# wave.net
KiCad netlist of a schematic drawn in Altium Designer
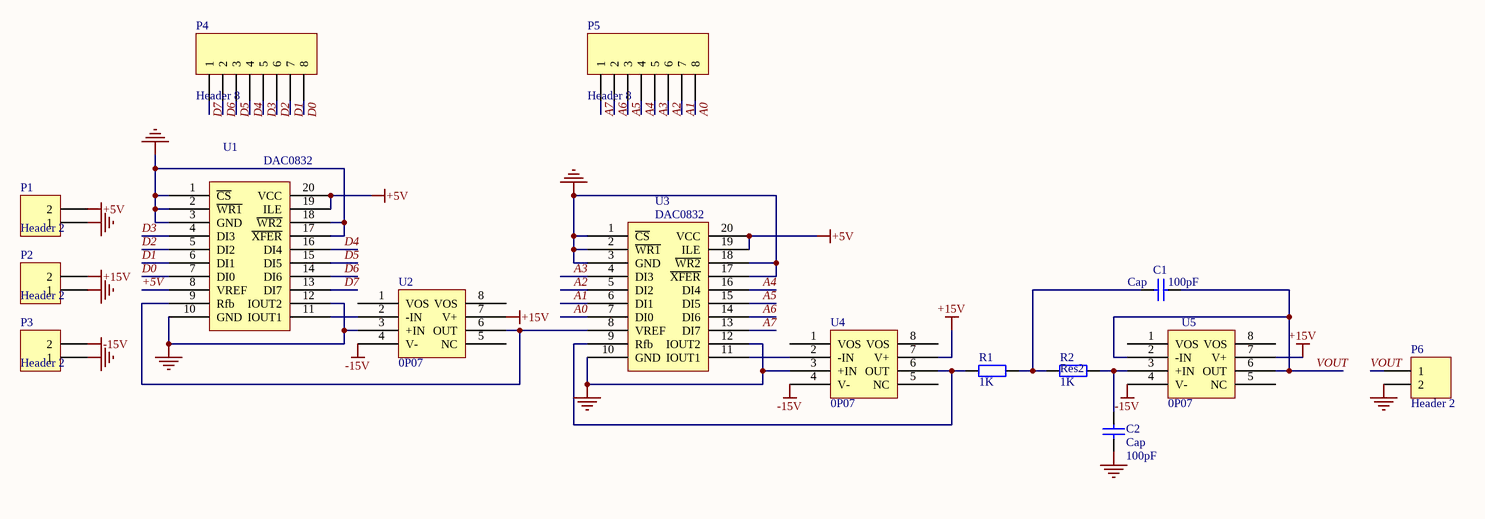
[diagram p0: wave.SchDoc]

(export (version "E")
  (design (tool "Eeschema 10.0.6"))
  (components
    (comp (ref "C1")
      (value "Cap")
      (footprint "RAD-0.3")
      (description "Capacitor")
      (fields (field (name "ALTIUM_VALUE") "100pF") (field (name "PUBLISHER") "Altium Limited"))
      (libsource (lib "Miscellaneous Devices") (part "Cap"))
    )
    (comp (ref "C2")
      (value "Cap")
      (footprint "RAD-0.3")
      (description "Capacitor")
      (fields (field (name "ALTIUM_VALUE") "100pF") (field (name "PUBLISHER") "Altium Limited"))
      (libsource (lib "Miscellaneous Devices") (part "Cap"))
    )
    (comp (ref "P1")
      (value "Header 2")
      (footprint "HDR1X2")
      (description "Header, 2-Pin")
      (fields (field (name "PUBLISHER") "Altium Limited"))
      (libsource (lib "Miscellaneous Connectors") (part "Header 2"))
    )
    (comp (ref "P2")
      (value "Header 2")
      (footprint "HDR1X2")
      (description "Header, 2-Pin")
      (fields (field (name "PUBLISHER") "Altium Limited"))
      (libsource (lib "Miscellaneous Connectors") (part "Header 2"))
    )
    (comp (ref "P3")
      (value "Header 2")
      (footprint "HDR1X2")
      (description "Header, 2-Pin")
      (fields (field (name "PUBLISHER") "Altium Limited"))
      (libsource (lib "Miscellaneous Connectors") (part "Header 2"))
    )
    (comp (ref "P4")
      (value "Header 8")
      (footprint "HDR1X8")
      (description "Header, 8-Pin")
      (fields (field (name "PUBLISHER") "Altium Limited"))
      (libsource (lib "Miscellaneous Connectors") (part "Header 8"))
    )
    (comp (ref "P5")
      (value "Header 8")
      (footprint "HDR1X8")
      (description "Header, 8-Pin")
      (fields (field (name "PUBLISHER") "Altium Limited"))
      (libsource (lib "Miscellaneous Connectors") (part "Header 8"))
    )
    (comp (ref "P6")
      (value "Header 2")
      (footprint "HDR1X2")
      (description "Header, 2-Pin")
      (fields (field (name "PUBLISHER") "Altium Limited"))
      (libsource (lib "") (part "Header 2_1"))
    )
    (comp (ref "R1")
      (value "1K")
      (footprint "AXIAL-0.4")
      (description "Resistor")
      (fields (field (name "Comment") "Res2") (field (name "PUBLISHER") "Altium Limited"))
      (libsource (lib "Miscellaneous Devices") (part "Res2"))
    )
    (comp (ref "R2")
      (value "Res2")
      (footprint "AXIAL-0.4")
      (description "Resistor")
      (fields (field (name "ALTIUM_VALUE") "1K") (field (name "PUBLISHER") "Altium Limited"))
      (libsource (lib "Miscellaneous Devices") (part "Res2"))
    )
    (comp (ref "U1")
      (value "DAC0832")
      (footprint "DIP-20")
      (libsource (lib "My sch Library") (part "DAC0832"))
    )
    (comp (ref "U2") (value "0P07") (footprint "DIP-8") (libsource (lib "My sch Library") (part "OP07")))
    (comp (ref "U3")
      (value "DAC0832")
      (footprint "DIP-20")
      (libsource (lib "My sch Library") (part "DAC0832"))
    )
    (comp (ref "U4") (value "0P07") (footprint "DIP-8") (libsource (lib "My sch Library") (part "OP07")))
    (comp (ref "U5") (value "0P07") (footprint "DIP-8") (libsource (lib "My sch Library") (part "OP07")))
  )
  (nets
    (net (code "1") (name "+5V") (class "Default")
      (node (ref "P1") (pin "2") (pinfunction "2_2") (pintype "passive"))
      (node (ref "U1") (pin "19") (pinfunction "ILE_19") (pintype "passive"))
      (node (ref "U1") (pin "20") (pinfunction "VCC_20") (pintype "passive"))
      (node (ref "U1") (pin "8") (pinfunction "VREF_8") (pintype "passive"))
      (node (ref "U3") (pin "19") (pinfunction "ILE_19") (pintype "passive"))
      (node (ref "U3") (pin "20") (pinfunction "VCC_20") (pintype "passive"))
    )
    (net (code "2") (name "+15V") (class "Default")
      (node (ref "P2") (pin "2") (pinfunction "2_2") (pintype "passive"))
      (node (ref "U2") (pin "7") (pinfunction "V+_7") (pintype "passive"))
      (node (ref "U4") (pin "7") (pinfunction "V+_7") (pintype "passive"))
      (node (ref "U5") (pin "7") (pinfunction "V+_7") (pintype "passive"))
    )
    (net (code "3") (name "-15V") (class "Default")
      (node (ref "P3") (pin "2") (pinfunction "2_2") (pintype "passive"))
      (node (ref "U2") (pin "4") (pinfunction "V-_4") (pintype "passive"))
      (node (ref "U4") (pin "4") (pinfunction "V-_4") (pintype "passive"))
      (node (ref "U5") (pin "4") (pinfunction "V-_4") (pintype "passive"))
    )
    (net (code "4") (name "/A0") (class "Default")
      (node (ref "P5") (pin "8") (pinfunction "8_8") (pintype "passive"))
      (node (ref "U3") (pin "7") (pinfunction "DI0_7") (pintype "passive"))
    )
    (net (code "5") (name "/A1") (class "Default")
      (node (ref "P5") (pin "7") (pinfunction "7_7") (pintype "passive"))
      (node (ref "U3") (pin "6") (pinfunction "DI1_6") (pintype "passive"))
    )
    (net (code "6") (name "/A2") (class "Default")
      (node (ref "P5") (pin "6") (pinfunction "6_6") (pintype "passive"))
      (node (ref "U3") (pin "5") (pinfunction "DI2_5") (pintype "passive"))
    )
    (net (code "7") (name "/A3") (class "Default")
      (node (ref "P5") (pin "5") (pinfunction "5_5") (pintype "passive"))
      (node (ref "U3") (pin "4") (pinfunction "DI3_4") (pintype "passive"))
    )
    (net (code "8") (name "/A4") (class "Default")
      (node (ref "P5") (pin "4") (pinfunction "4_4") (pintype "passive"))
      (node (ref "U3") (pin "16") (pinfunction "DI4_16") (pintype "passive"))
    )
    (net (code "9") (name "/A5") (class "Default")
      (node (ref "P5") (pin "3") (pinfunction "3_3") (pintype "passive"))
      (node (ref "U3") (pin "15") (pinfunction "DI5_15") (pintype "passive"))
    )
    (net (code "10") (name "/A6") (class "Default")
      (node (ref "P5") (pin "2") (pinfunction "2_2") (pintype "passive"))
      (node (ref "U3") (pin "14") (pinfunction "DI6_14") (pintype "passive"))
    )
    (net (code "11") (name "/A7") (class "Default")
      (node (ref "P5") (pin "1") (pinfunction "1_1") (pintype "passive"))
      (node (ref "U3") (pin "13") (pinfunction "DI7_13") (pintype "passive"))
    )
    (net (code "12") (name "/D0") (class "Default")
      (node (ref "P4") (pin "8") (pinfunction "8_8") (pintype "passive"))
      (node (ref "U1") (pin "7") (pinfunction "DI0_7") (pintype "passive"))
    )
    (net (code "13") (name "/D1") (class "Default")
      (node (ref "P4") (pin "7") (pinfunction "7_7") (pintype "passive"))
      (node (ref "U1") (pin "6") (pinfunction "DI1_6") (pintype "passive"))
    )
    (net (code "14") (name "/D2") (class "Default")
      (node (ref "P4") (pin "6") (pinfunction "6_6") (pintype "passive"))
      (node (ref "U1") (pin "5") (pinfunction "DI2_5") (pintype "passive"))
    )
    (net (code "15") (name "/D3") (class "Default")
      (node (ref "P4") (pin "5") (pinfunction "5_5") (pintype "passive"))
      (node (ref "U1") (pin "4") (pinfunction "DI3_4") (pintype "passive"))
    )
    (net (code "16") (name "/D4") (class "Default")
      (node (ref "P4") (pin "4") (pinfunction "4_4") (pintype "passive"))
      (node (ref "U1") (pin "16") (pinfunction "DI4_16") (pintype "passive"))
    )
    (net (code "17") (name "/D5") (class "Default")
      (node (ref "P4") (pin "3") (pinfunction "3_3") (pintype "passive"))
      (node (ref "U1") (pin "15") (pinfunction "DI5_15") (pintype "passive"))
    )
    (net (code "18") (name "/D6") (class "Default")
      (node (ref "P4") (pin "2") (pinfunction "2_2") (pintype "passive"))
      (node (ref "U1") (pin "14") (pinfunction "DI6_14") (pintype "passive"))
    )
    (net (code "19") (name "/D7") (class "Default")
      (node (ref "P4") (pin "1") (pinfunction "1_1") (pintype "passive"))
      (node (ref "U1") (pin "13") (pinfunction "DI7_13") (pintype "passive"))
    )
    (net (code "20") (name "/VOUT") (class "Default")
      (node (ref "C1") (pin "2") (pinfunction "2_2") (pintype "passive"))
      (node (ref "P6") (pin "1") (pinfunction "1_1") (pintype "passive"))
      (node (ref "U5") (pin "2") (pinfunction "-IN_2") (pintype "passive"))
      (node (ref "U5") (pin "6") (pinfunction "OUT_6") (pintype "passive"))
    )
    (net (code "21") (name "GND") (class "Default")
      (node (ref "C2") (pin "2") (pinfunction "2_2") (pintype "passive"))
      (node (ref "P1") (pin "1") (pinfunction "1_1") (pintype "passive"))
      (node (ref "P2") (pin "1") (pinfunction "1_1") (pintype "passive"))
      (node (ref "P3") (pin "1") (pinfunction "1_1") (pintype "passive"))
      (node (ref "P6") (pin "2") (pinfunction "2_2") (pintype "passive"))
      (node (ref "U1") (pin "1") (pinfunction "~{CS}_1") (pintype "passive"))
      (node (ref "U1") (pin "10") (pinfunction "GND_10") (pintype "passive"))
      (node (ref "U1") (pin "12") (pinfunction "IOUT2_12") (pintype "passive"))
      (node (ref "U1") (pin "17") (pinfunction "~{XFER}_17") (pintype "passive"))
      (node (ref "U1") (pin "18") (pinfunction "~{WR2}_18") (pintype "passive"))
      (node (ref "U1") (pin "2") (pinfunction "~{WR1}_2") (pintype "passive"))
      (node (ref "U1") (pin "3") (pinfunction "GND_3") (pintype "passive"))
      (node (ref "U2") (pin "3") (pinfunction "+IN_3") (pintype "passive"))
      (node (ref "U3") (pin "1") (pinfunction "~{CS}_1") (pintype "passive"))
      (node (ref "U3") (pin "10") (pinfunction "GND_10") (pintype "passive"))
      (node (ref "U3") (pin "12") (pinfunction "IOUT2_12") (pintype "passive"))
      (node (ref "U3") (pin "17") (pinfunction "~{XFER}_17") (pintype "passive"))
      (node (ref "U3") (pin "18") (pinfunction "~{WR2}_18") (pintype "passive"))
      (node (ref "U3") (pin "2") (pinfunction "~{WR1}_2") (pintype "passive"))
      (node (ref "U3") (pin "3") (pinfunction "GND_3") (pintype "passive"))
      (node (ref "U4") (pin "3") (pinfunction "+IN_3") (pintype "passive"))
    )
    (net (code "22") (name "Net-(C1-Pad1)") (class "Default")
      (node (ref "C1") (pin "1") (pinfunction "1_1") (pintype "passive"))
      (node (ref "R1") (pin "2") (pinfunction "2_2") (pintype "passive"))
      (node (ref "R2") (pin "1") (pinfunction "1_1") (pintype "passive"))
    )
    (net (code "23") (name "Net-(U1-IOUT1)") (class "Default")
      (node (ref "U1") (pin "11") (pinfunction "IOUT1_11") (pintype "passive"))
      (node (ref "U2") (pin "2") (pinfunction "-IN_2") (pintype "passive"))
    )
    (net (code "24") (name "Net-(U1-Rfb)") (class "Default")
      (node (ref "U1") (pin "9") (pinfunction "Rfb_9") (pintype "passive"))
      (node (ref "U2") (pin "6") (pinfunction "OUT_6") (pintype "passive"))
      (node (ref "U3") (pin "8") (pinfunction "VREF_8") (pintype "passive"))
    )
    (net (code "25") (name "Net-(U3-IOUT1)") (class "Default")
      (node (ref "U3") (pin "11") (pinfunction "IOUT1_11") (pintype "passive"))
      (node (ref "U4") (pin "2") (pinfunction "-IN_2") (pintype "passive"))
    )
    (net (code "26") (name "Net-(U3-Rfb)") (class "Default")
      (node (ref "R1") (pin "1") (pinfunction "1_1") (pintype "passive"))
      (node (ref "U3") (pin "9") (pinfunction "Rfb_9") (pintype "passive"))
      (node (ref "U4") (pin "6") (pinfunction "OUT_6") (pintype "passive"))
    )
    (net (code "27") (name "Net-(U5-+IN)") (class "Default")
      (node (ref "C2") (pin "1") (pinfunction "1_1") (pintype "passive"))
      (node (ref "R2") (pin "2") (pinfunction "2_2") (pintype "passive"))
      (node (ref "U5") (pin "3") (pinfunction "+IN_3") (pintype "passive"))
    )
    (net (code "28") (name "unconnected-(U2-NC-Pad5)") (class "Default")
      (node (ref "U2") (pin "5") (pinfunction "NC_5") (pintype "passive"))
    )
    (net (code "29") (name "unconnected-(U2-VOS-Pad1)") (class "Default")
      (node (ref "U2") (pin "1") (pinfunction "VOS_1") (pintype "passive"))
    )
    (net (code "30") (name "unconnected-(U2-VOS-Pad8)") (class "Default")
      (node (ref "U2") (pin "8") (pinfunction "VOS_8") (pintype "passive"))
    )
    (net (code "31") (name "unconnected-(U4-NC-Pad5)") (class "Default")
      (node (ref "U4") (pin "5") (pinfunction "NC_5") (pintype "passive"))
    )
    (net (code "32") (name "unconnected-(U4-VOS-Pad1)") (class "Default")
      (node (ref "U4") (pin "1") (pinfunction "VOS_1") (pintype "passive"))
    )
    (net (code "33") (name "unconnected-(U4-VOS-Pad8)") (class "Default")
      (node (ref "U4") (pin "8") (pinfunction "VOS_8") (pintype "passive"))
    )
    (net (code "34") (name "unconnected-(U5-NC-Pad5)") (class "Default")
      (node (ref "U5") (pin "5") (pinfunction "NC_5") (pintype "passive"))
    )
    (net (code "35") (name "unconnected-(U5-VOS-Pad1)") (class "Default")
      (node (ref "U5") (pin "1") (pinfunction "VOS_1") (pintype "passive"))
    )
    (net (code "36") (name "unconnected-(U5-VOS-Pad8)") (class "Default")
      (node (ref "U5") (pin "8") (pinfunction "VOS_8") (pintype "passive"))
    )
  )
)
